# MotherBoard.net
KiCad netlist of a schematic drawn in EAGLE
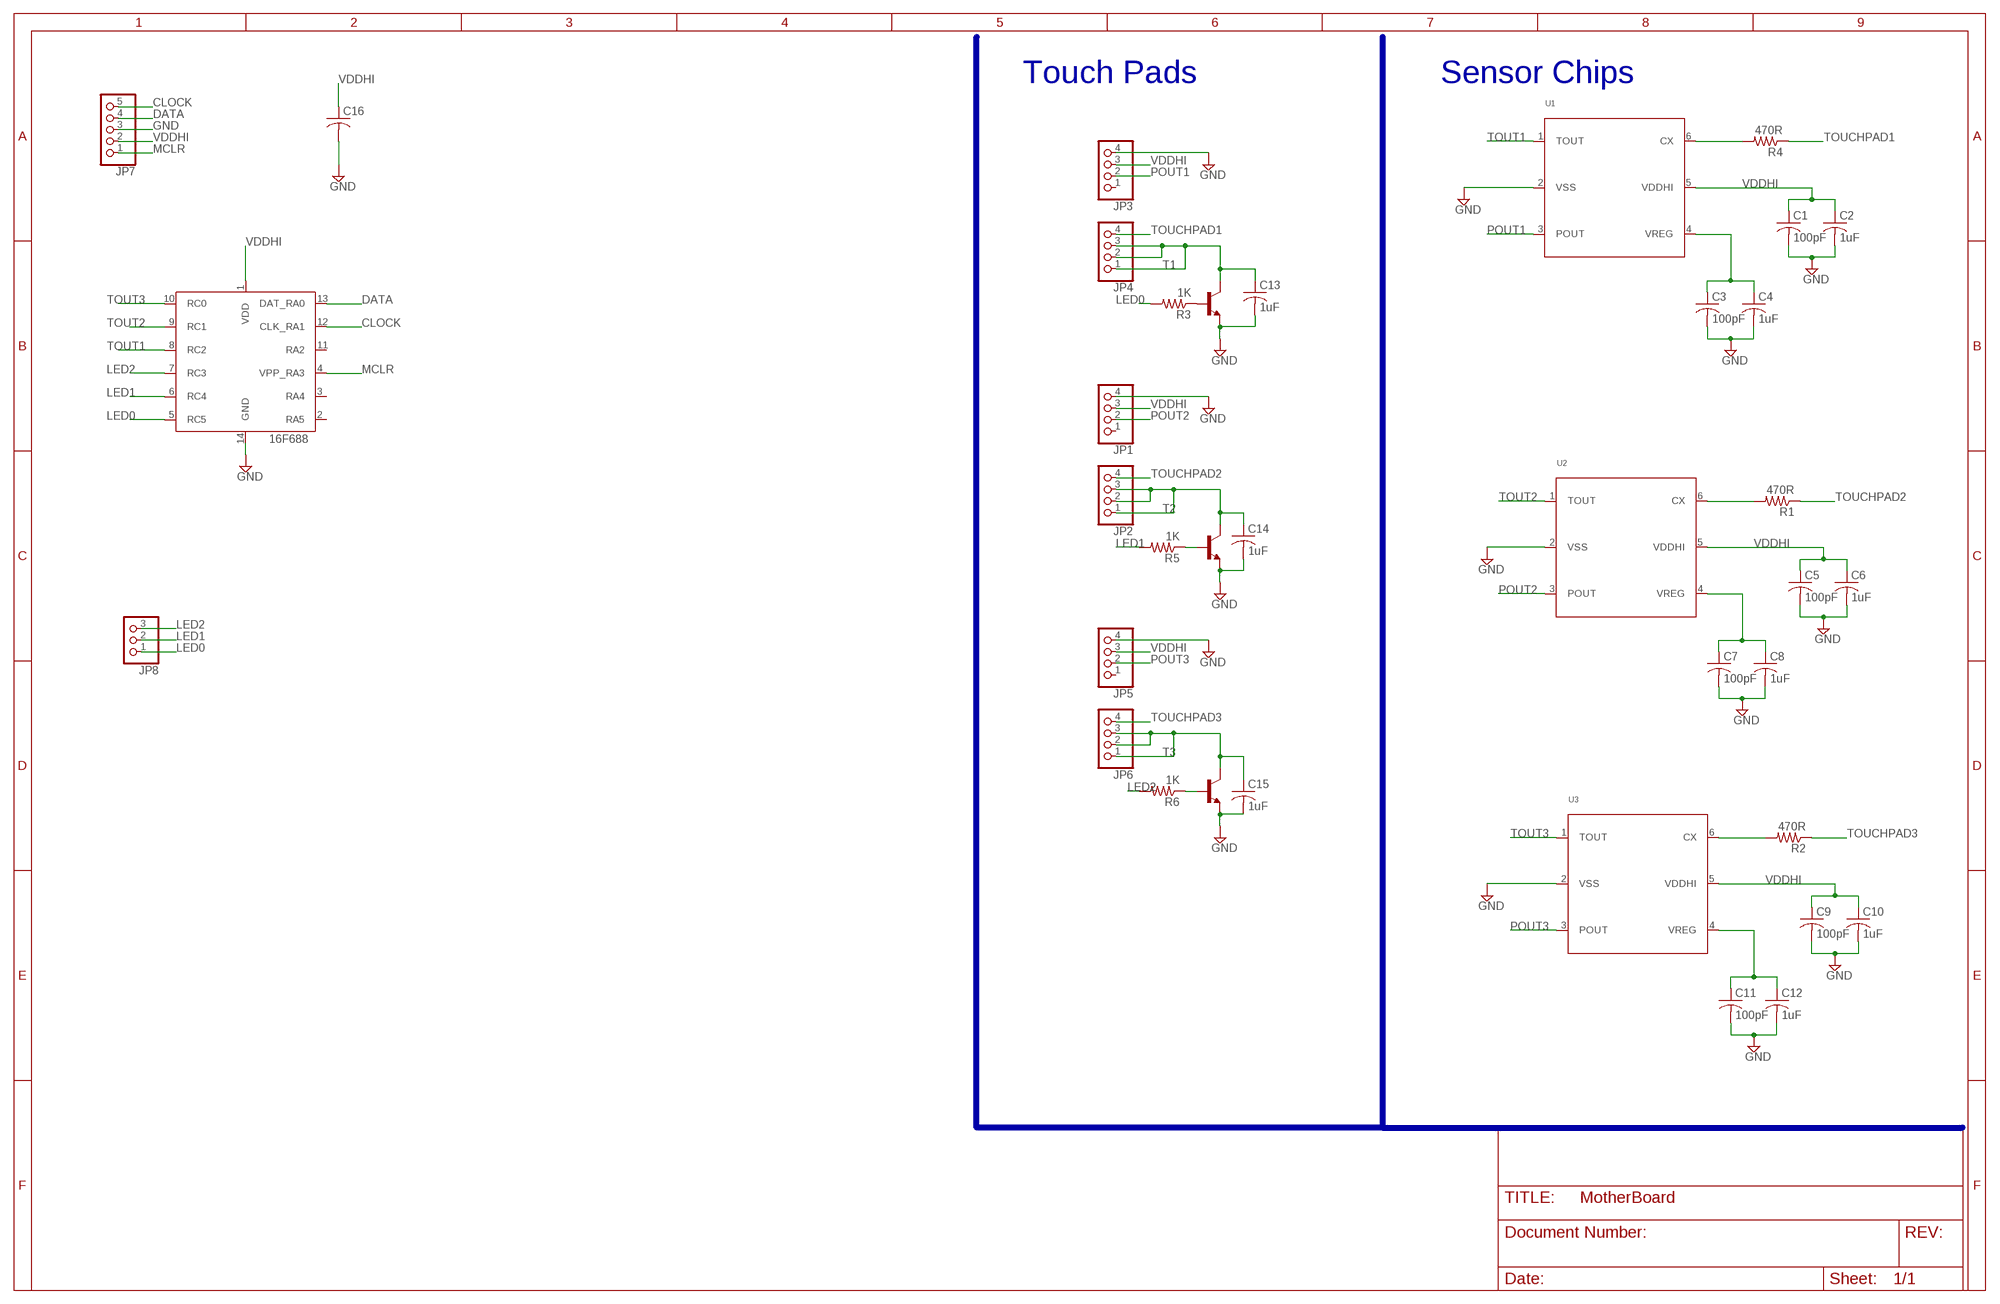
[diagram p0: schematic, sheet 1]

(export (version "E")
  (design (tool "Eeschema 10.0.6"))
  (components
    (comp (ref "C1")
      (value "100pF")
      (footprint "eagle-import:C0603K")
      (libsource (lib "eagle-import") (part "C-USC0603K"))
    )
    (comp (ref "C2")
      (value "1uF")
      (footprint "eagle-import:C0603K")
      (libsource (lib "eagle-import") (part "C-USC0603K"))
    )
    (comp (ref "C3")
      (value "100pF")
      (footprint "eagle-import:C0603K")
      (libsource (lib "eagle-import") (part "C-USC0603K"))
    )
    (comp (ref "C4")
      (value "1uF")
      (footprint "eagle-import:C0603K")
      (libsource (lib "eagle-import") (part "C-USC0603K"))
    )
    (comp (ref "C5")
      (value "100pF")
      (footprint "eagle-import:C0603K")
      (libsource (lib "eagle-import") (part "C-USC0603K"))
    )
    (comp (ref "C6")
      (value "1uF")
      (footprint "eagle-import:C0603K")
      (libsource (lib "eagle-import") (part "C-USC0603K"))
    )
    (comp (ref "C7")
      (value "100pF")
      (footprint "eagle-import:C0603K")
      (libsource (lib "eagle-import") (part "C-USC0603K"))
    )
    (comp (ref "C8")
      (value "1uF")
      (footprint "eagle-import:C0603K")
      (libsource (lib "eagle-import") (part "C-USC0603K"))
    )
    (comp (ref "C9")
      (value "100pF")
      (footprint "eagle-import:C0603K")
      (libsource (lib "eagle-import") (part "C-USC0603K"))
    )
    (comp (ref "C10")
      (value "1uF")
      (footprint "eagle-import:C0603K")
      (libsource (lib "eagle-import") (part "C-USC0603K"))
    )
    (comp (ref "C11")
      (value "100pF")
      (footprint "eagle-import:C0603K")
      (libsource (lib "eagle-import") (part "C-USC0603K"))
    )
    (comp (ref "C12")
      (value "1uF")
      (footprint "eagle-import:C0603K")
      (libsource (lib "eagle-import") (part "C-USC0603K"))
    )
    (comp (ref "C13")
      (value "1uF")
      (footprint "eagle-import:C0603K")
      (libsource (lib "eagle-import") (part "C-USC0603K"))
    )
    (comp (ref "C14")
      (value "1uF")
      (footprint "eagle-import:C0603K")
      (libsource (lib "eagle-import") (part "C-USC0603K"))
    )
    (comp (ref "C15")
      (value "1uF")
      (footprint "eagle-import:C0603K")
      (libsource (lib "eagle-import") (part "C-USC0603K"))
    )
    (comp (ref "C16")
      (value "C-USC1206")
      (footprint "eagle-import:C1206")
      (libsource (lib "eagle-import") (part "C-USC1206"))
    )
    (comp (ref "JP1")
      (value "PINHD-1X4")
      (footprint "eagle-import:1X04")
      (libsource (lib "eagle-import") (part "PINHD-1X4"))
    )
    (comp (ref "JP2")
      (value "PINHD-1X4")
      (footprint "eagle-import:1X04")
      (libsource (lib "eagle-import") (part "PINHD-1X4"))
    )
    (comp (ref "JP3")
      (value "PINHD-1X4")
      (footprint "eagle-import:1X04")
      (libsource (lib "eagle-import") (part "PINHD-1X4"))
    )
    (comp (ref "JP4")
      (value "PINHD-1X4")
      (footprint "eagle-import:1X04")
      (libsource (lib "eagle-import") (part "PINHD-1X4"))
    )
    (comp (ref "JP5")
      (value "PINHD-1X4")
      (footprint "eagle-import:1X04")
      (libsource (lib "eagle-import") (part "PINHD-1X4"))
    )
    (comp (ref "JP6")
      (value "PINHD-1X4")
      (footprint "eagle-import:1X04")
      (libsource (lib "eagle-import") (part "PINHD-1X4"))
    )
    (comp (ref "JP7")
      (value "PINHD-1X5")
      (footprint "eagle-import:1X05")
      (libsource (lib "eagle-import") (part "PINHD-1X5"))
    )
    (comp (ref "JP8")
      (value "PINHD-1X3")
      (footprint "eagle-import:1X03")
      (libsource (lib "eagle-import") (part "PINHD-1X3"))
    )
    (comp (ref "R1")
      (value "470R")
      (footprint "eagle-import:R0603")
      (libsource (lib "eagle-import") (part "R-US_R0603"))
    )
    (comp (ref "R2")
      (value "470R")
      (footprint "eagle-import:R0603")
      (libsource (lib "eagle-import") (part "R-US_R0603"))
    )
    (comp (ref "R3")
      (value "1K")
      (footprint "eagle-import:R0603")
      (libsource (lib "eagle-import") (part "R-US_R0603"))
    )
    (comp (ref "R4")
      (value "470R")
      (footprint "eagle-import:R0603")
      (libsource (lib "eagle-import") (part "R-US_R0603"))
    )
    (comp (ref "R5")
      (value "1K")
      (footprint "eagle-import:R0603")
      (libsource (lib "eagle-import") (part "R-US_R0603"))
    )
    (comp (ref "R6")
      (value "1K")
      (footprint "eagle-import:R0603")
      (libsource (lib "eagle-import") (part "R-US_R0603"))
    )
    (comp (ref "T1")
      (value "BC818-NPN-SOT23-BEC")
      (footprint "eagle-import:SOT23-BEC")
      (libsource (lib "eagle-import") (part "-NPN-SOT23-BECBC818"))
    )
    (comp (ref "T2")
      (value "BC818-NPN-SOT23-BEC")
      (footprint "eagle-import:SOT23-BEC")
      (libsource (lib "eagle-import") (part "-NPN-SOT23-BECBC818"))
    )
    (comp (ref "T3")
      (value "BC818-NPN-SOT23-BEC")
      (footprint "eagle-import:SOT23-BEC")
      (libsource (lib "eagle-import") (part "-NPN-SOT23-BECBC818"))
    )
    (comp (ref "U$1")
      (value "PIC16F688SOIC14")
      (footprint "eagle-import:SOIC14")
      (libsource (lib "eagle-import") (part "PIC16F688SOIC14"))
    )
    (comp (ref "U1")
      (value "IQS127")
      (footprint "eagle-import:SOT23-6")
      (libsource (lib "eagle-import") (part "IQS127"))
    )
    (comp (ref "U2")
      (value "IQS127")
      (footprint "eagle-import:SOT23-6")
      (libsource (lib "eagle-import") (part "IQS127"))
    )
    (comp (ref "U3")
      (value "IQS127")
      (footprint "eagle-import:SOT23-6")
      (libsource (lib "eagle-import") (part "IQS127"))
    )
  )
  (nets
    (net (code "1") (name "/CLOCK") (class "Default")
      (node (ref "JP7") (pin "5") (pinfunction "5_5") (pintype "passive"))
      (node (ref "U$1") (pin "12") (pinfunction "CLK_RA1_12") (pintype "passive"))
    )
    (net (code "2") (name "/DATA") (class "Default")
      (node (ref "JP7") (pin "4") (pinfunction "4_4") (pintype "passive"))
      (node (ref "U$1") (pin "13") (pinfunction "DAT_RA0_13") (pintype "passive"))
    )
    (net (code "3") (name "/LED0") (class "Default")
      (node (ref "JP8") (pin "1") (pinfunction "1_1") (pintype "passive"))
      (node (ref "R3") (pin "2") (pinfunction "2_2") (pintype "passive"))
      (node (ref "U$1") (pin "5") (pinfunction "RC5_5") (pintype "passive"))
    )
    (net (code "4") (name "/LED1") (class "Default")
      (node (ref "JP8") (pin "2") (pinfunction "2_2") (pintype "passive"))
      (node (ref "R5") (pin "2") (pinfunction "2_2") (pintype "passive"))
      (node (ref "U$1") (pin "6") (pinfunction "RC4_6") (pintype "passive"))
    )
    (net (code "5") (name "/LED2") (class "Default")
      (node (ref "JP8") (pin "3") (pinfunction "3_3") (pintype "passive"))
      (node (ref "R6") (pin "2") (pinfunction "2_2") (pintype "passive"))
      (node (ref "U$1") (pin "7") (pinfunction "RC3_7") (pintype "passive"))
    )
    (net (code "6") (name "/MCLR") (class "Default")
      (node (ref "JP7") (pin "1") (pinfunction "1_1") (pintype "passive"))
      (node (ref "U$1") (pin "4") (pinfunction "VPP_RA3_4") (pintype "passive"))
    )
    (net (code "7") (name "/POUT1") (class "Default")
      (node (ref "JP3") (pin "2") (pinfunction "2_2") (pintype "passive"))
      (node (ref "U1") (pin "3") (pinfunction "POUT_3") (pintype "output"))
    )
    (net (code "8") (name "/POUT2") (class "Default")
      (node (ref "JP1") (pin "2") (pinfunction "2_2") (pintype "passive"))
      (node (ref "U2") (pin "3") (pinfunction "POUT_3") (pintype "output"))
    )
    (net (code "9") (name "/POUT3") (class "Default")
      (node (ref "JP5") (pin "2") (pinfunction "2_2") (pintype "passive"))
      (node (ref "U3") (pin "3") (pinfunction "POUT_3") (pintype "output"))
    )
    (net (code "10") (name "/TOUCHPAD1") (class "Default")
      (node (ref "JP4") (pin "4") (pinfunction "4_4") (pintype "passive"))
      (node (ref "R4") (pin "1") (pinfunction "1_1") (pintype "passive"))
    )
    (net (code "11") (name "/TOUCHPAD2") (class "Default")
      (node (ref "JP2") (pin "4") (pinfunction "4_4") (pintype "passive"))
      (node (ref "R1") (pin "1") (pinfunction "1_1") (pintype "passive"))
    )
    (net (code "12") (name "/TOUCHPAD3") (class "Default")
      (node (ref "JP6") (pin "4") (pinfunction "4_4") (pintype "passive"))
      (node (ref "R2") (pin "1") (pinfunction "1_1") (pintype "passive"))
    )
    (net (code "13") (name "/TOUT1") (class "Default")
      (node (ref "U$1") (pin "8") (pinfunction "RC2_8") (pintype "passive"))
      (node (ref "U1") (pin "1") (pinfunction "TOUT_1") (pintype "output"))
    )
    (net (code "14") (name "/TOUT2") (class "Default")
      (node (ref "U$1") (pin "9") (pinfunction "RC1_9") (pintype "passive"))
      (node (ref "U2") (pin "1") (pinfunction "TOUT_1") (pintype "output"))
    )
    (net (code "15") (name "/TOUT3") (class "Default")
      (node (ref "U$1") (pin "10") (pinfunction "RC0_10") (pintype "passive"))
      (node (ref "U3") (pin "1") (pinfunction "TOUT_1") (pintype "output"))
    )
    (net (code "16") (name "/VDDHI") (class "Default")
      (node (ref "C1") (pin "1") (pinfunction "1_1") (pintype "passive"))
      (node (ref "C10") (pin "1") (pinfunction "1_1") (pintype "passive"))
      (node (ref "C16") (pin "1") (pinfunction "1_1") (pintype "passive"))
      (node (ref "C2") (pin "1") (pinfunction "1_1") (pintype "passive"))
      (node (ref "C5") (pin "1") (pinfunction "1_1") (pintype "passive"))
      (node (ref "C6") (pin "1") (pinfunction "1_1") (pintype "passive"))
      (node (ref "C9") (pin "1") (pinfunction "1_1") (pintype "passive"))
      (node (ref "JP1") (pin "3") (pinfunction "3_3") (pintype "passive"))
      (node (ref "JP3") (pin "3") (pinfunction "3_3") (pintype "passive"))
      (node (ref "JP5") (pin "3") (pinfunction "3_3") (pintype "passive"))
      (node (ref "JP7") (pin "2") (pinfunction "2_2") (pintype "passive"))
      (node (ref "U$1") (pin "1") (pinfunction "VDD_1") (pintype "passive"))
      (node (ref "U1") (pin "5") (pinfunction "VDDHI_5") (pintype "power_in"))
      (node (ref "U2") (pin "5") (pinfunction "VDDHI_5") (pintype "power_in"))
      (node (ref "U3") (pin "5") (pinfunction "VDDHI_5") (pintype "power_in"))
    )
    (net (code "17") (name "GND") (class "Default")
      (node (ref "C1") (pin "2") (pinfunction "2_2") (pintype "passive"))
      (node (ref "C10") (pin "2") (pinfunction "2_2") (pintype "passive"))
      (node (ref "C11") (pin "2") (pinfunction "2_2") (pintype "passive"))
      (node (ref "C12") (pin "2") (pinfunction "2_2") (pintype "passive"))
      (node (ref "C13") (pin "2") (pinfunction "2_2") (pintype "passive"))
      (node (ref "C14") (pin "2") (pinfunction "2_2") (pintype "passive"))
      (node (ref "C15") (pin "2") (pinfunction "2_2") (pintype "passive"))
      (node (ref "C16") (pin "2") (pinfunction "2_2") (pintype "passive"))
      (node (ref "C2") (pin "2") (pinfunction "2_2") (pintype "passive"))
      (node (ref "C3") (pin "2") (pinfunction "2_2") (pintype "passive"))
      (node (ref "C4") (pin "2") (pinfunction "2_2") (pintype "passive"))
      (node (ref "C5") (pin "2") (pinfunction "2_2") (pintype "passive"))
      (node (ref "C6") (pin "2") (pinfunction "2_2") (pintype "passive"))
      (node (ref "C7") (pin "2") (pinfunction "2_2") (pintype "passive"))
      (node (ref "C8") (pin "2") (pinfunction "2_2") (pintype "passive"))
      (node (ref "C9") (pin "2") (pinfunction "2_2") (pintype "passive"))
      (node (ref "JP1") (pin "4") (pinfunction "4_4") (pintype "passive"))
      (node (ref "JP3") (pin "4") (pinfunction "4_4") (pintype "passive"))
      (node (ref "JP5") (pin "4") (pinfunction "4_4") (pintype "passive"))
      (node (ref "JP7") (pin "3") (pinfunction "3_3") (pintype "passive"))
      (node (ref "T1") (pin "E") (pinfunction "E_E") (pintype "passive"))
      (node (ref "T2") (pin "E") (pinfunction "E_E") (pintype "passive"))
      (node (ref "T3") (pin "E") (pinfunction "E_E") (pintype "passive"))
      (node (ref "U$1") (pin "14") (pinfunction "GND_14") (pintype "passive"))
      (node (ref "U1") (pin "2") (pinfunction "VSS_2") (pintype "power_in"))
      (node (ref "U2") (pin "2") (pinfunction "VSS_2") (pintype "power_in"))
      (node (ref "U3") (pin "2") (pinfunction "VSS_2") (pintype "power_in"))
    )
    (net (code "18") (name "Net-(C13-Pad1)") (class "Default")
      (node (ref "C13") (pin "1") (pinfunction "1_1") (pintype "passive"))
      (node (ref "JP4") (pin "1") (pinfunction "1_1") (pintype "passive"))
      (node (ref "JP4") (pin "2") (pinfunction "2_2") (pintype "passive"))
      (node (ref "JP4") (pin "3") (pinfunction "3_3") (pintype "passive"))
      (node (ref "T1") (pin "C") (pinfunction "C_C") (pintype "passive"))
    )
    (net (code "19") (name "Net-(C14-Pad1)") (class "Default")
      (node (ref "C14") (pin "1") (pinfunction "1_1") (pintype "passive"))
      (node (ref "JP2") (pin "1") (pinfunction "1_1") (pintype "passive"))
      (node (ref "JP2") (pin "2") (pinfunction "2_2") (pintype "passive"))
      (node (ref "JP2") (pin "3") (pinfunction "3_3") (pintype "passive"))
      (node (ref "T2") (pin "C") (pinfunction "C_C") (pintype "passive"))
    )
    (net (code "20") (name "Net-(C15-Pad1)") (class "Default")
      (node (ref "C15") (pin "1") (pinfunction "1_1") (pintype "passive"))
      (node (ref "JP6") (pin "1") (pinfunction "1_1") (pintype "passive"))
      (node (ref "JP6") (pin "2") (pinfunction "2_2") (pintype "passive"))
      (node (ref "JP6") (pin "3") (pinfunction "3_3") (pintype "passive"))
      (node (ref "T3") (pin "C") (pinfunction "C_C") (pintype "passive"))
    )
    (net (code "21") (name "Net-(R3-Pad1)") (class "Default")
      (node (ref "R3") (pin "1") (pinfunction "1_1") (pintype "passive"))
      (node (ref "T1") (pin "B") (pinfunction "B_B") (pintype "passive"))
    )
    (net (code "22") (name "Net-(R5-Pad1)") (class "Default")
      (node (ref "R5") (pin "1") (pinfunction "1_1") (pintype "passive"))
      (node (ref "T2") (pin "B") (pinfunction "B_B") (pintype "passive"))
    )
    (net (code "23") (name "Net-(R6-Pad1)") (class "Default")
      (node (ref "R6") (pin "1") (pinfunction "1_1") (pintype "passive"))
      (node (ref "T3") (pin "B") (pinfunction "B_B") (pintype "passive"))
    )
    (net (code "24") (name "Net-(U1-CX)") (class "Default")
      (node (ref "R4") (pin "2") (pinfunction "2_2") (pintype "passive"))
      (node (ref "U1") (pin "6") (pinfunction "CX_6") (pintype "bidirectional"))
    )
    (net (code "25") (name "Net-(U1-VREG)") (class "Default")
      (node (ref "C3") (pin "1") (pinfunction "1_1") (pintype "passive"))
      (node (ref "C4") (pin "1") (pinfunction "1_1") (pintype "passive"))
      (node (ref "U1") (pin "4") (pinfunction "VREG_4") (pintype "bidirectional"))
    )
    (net (code "26") (name "Net-(U2-CX)") (class "Default")
      (node (ref "R1") (pin "2") (pinfunction "2_2") (pintype "passive"))
      (node (ref "U2") (pin "6") (pinfunction "CX_6") (pintype "bidirectional"))
    )
    (net (code "27") (name "Net-(U2-VREG)") (class "Default")
      (node (ref "C7") (pin "1") (pinfunction "1_1") (pintype "passive"))
      (node (ref "C8") (pin "1") (pinfunction "1_1") (pintype "passive"))
      (node (ref "U2") (pin "4") (pinfunction "VREG_4") (pintype "bidirectional"))
    )
    (net (code "28") (name "Net-(U3-CX)") (class "Default")
      (node (ref "R2") (pin "2") (pinfunction "2_2") (pintype "passive"))
      (node (ref "U3") (pin "6") (pinfunction "CX_6") (pintype "bidirectional"))
    )
    (net (code "29") (name "Net-(U3-VREG)") (class "Default")
      (node (ref "C11") (pin "1") (pinfunction "1_1") (pintype "passive"))
      (node (ref "C12") (pin "1") (pinfunction "1_1") (pintype "passive"))
      (node (ref "U3") (pin "4") (pinfunction "VREG_4") (pintype "bidirectional"))
    )
    (net (code "30") (name "unconnected-(JP1-Pad1)") (class "Default")
      (node (ref "JP1") (pin "1") (pinfunction "1_1") (pintype "passive"))
    )
    (net (code "31") (name "unconnected-(JP3-Pad1)") (class "Default")
      (node (ref "JP3") (pin "1") (pinfunction "1_1") (pintype "passive"))
    )
    (net (code "32") (name "unconnected-(JP5-Pad1)") (class "Default")
      (node (ref "JP5") (pin "1") (pinfunction "1_1") (pintype "passive"))
    )
    (net (code "33") (name "unconnected-(U$1-RA2-Pad11)") (class "Default")
      (node (ref "U$1") (pin "11") (pinfunction "RA2_11") (pintype "passive"))
    )
    (net (code "34") (name "unconnected-(U$1-RA4-Pad3)") (class "Default")
      (node (ref "U$1") (pin "3") (pinfunction "RA4_3") (pintype "passive"))
    )
    (net (code "35") (name "unconnected-(U$1-RA5-Pad2)") (class "Default")
      (node (ref "U$1") (pin "2") (pinfunction "RA5_2") (pintype "passive"))
    )
  )
)
